# PicKit2-v1_2.net
KiCad netlist of a schematic drawn in EAGLE
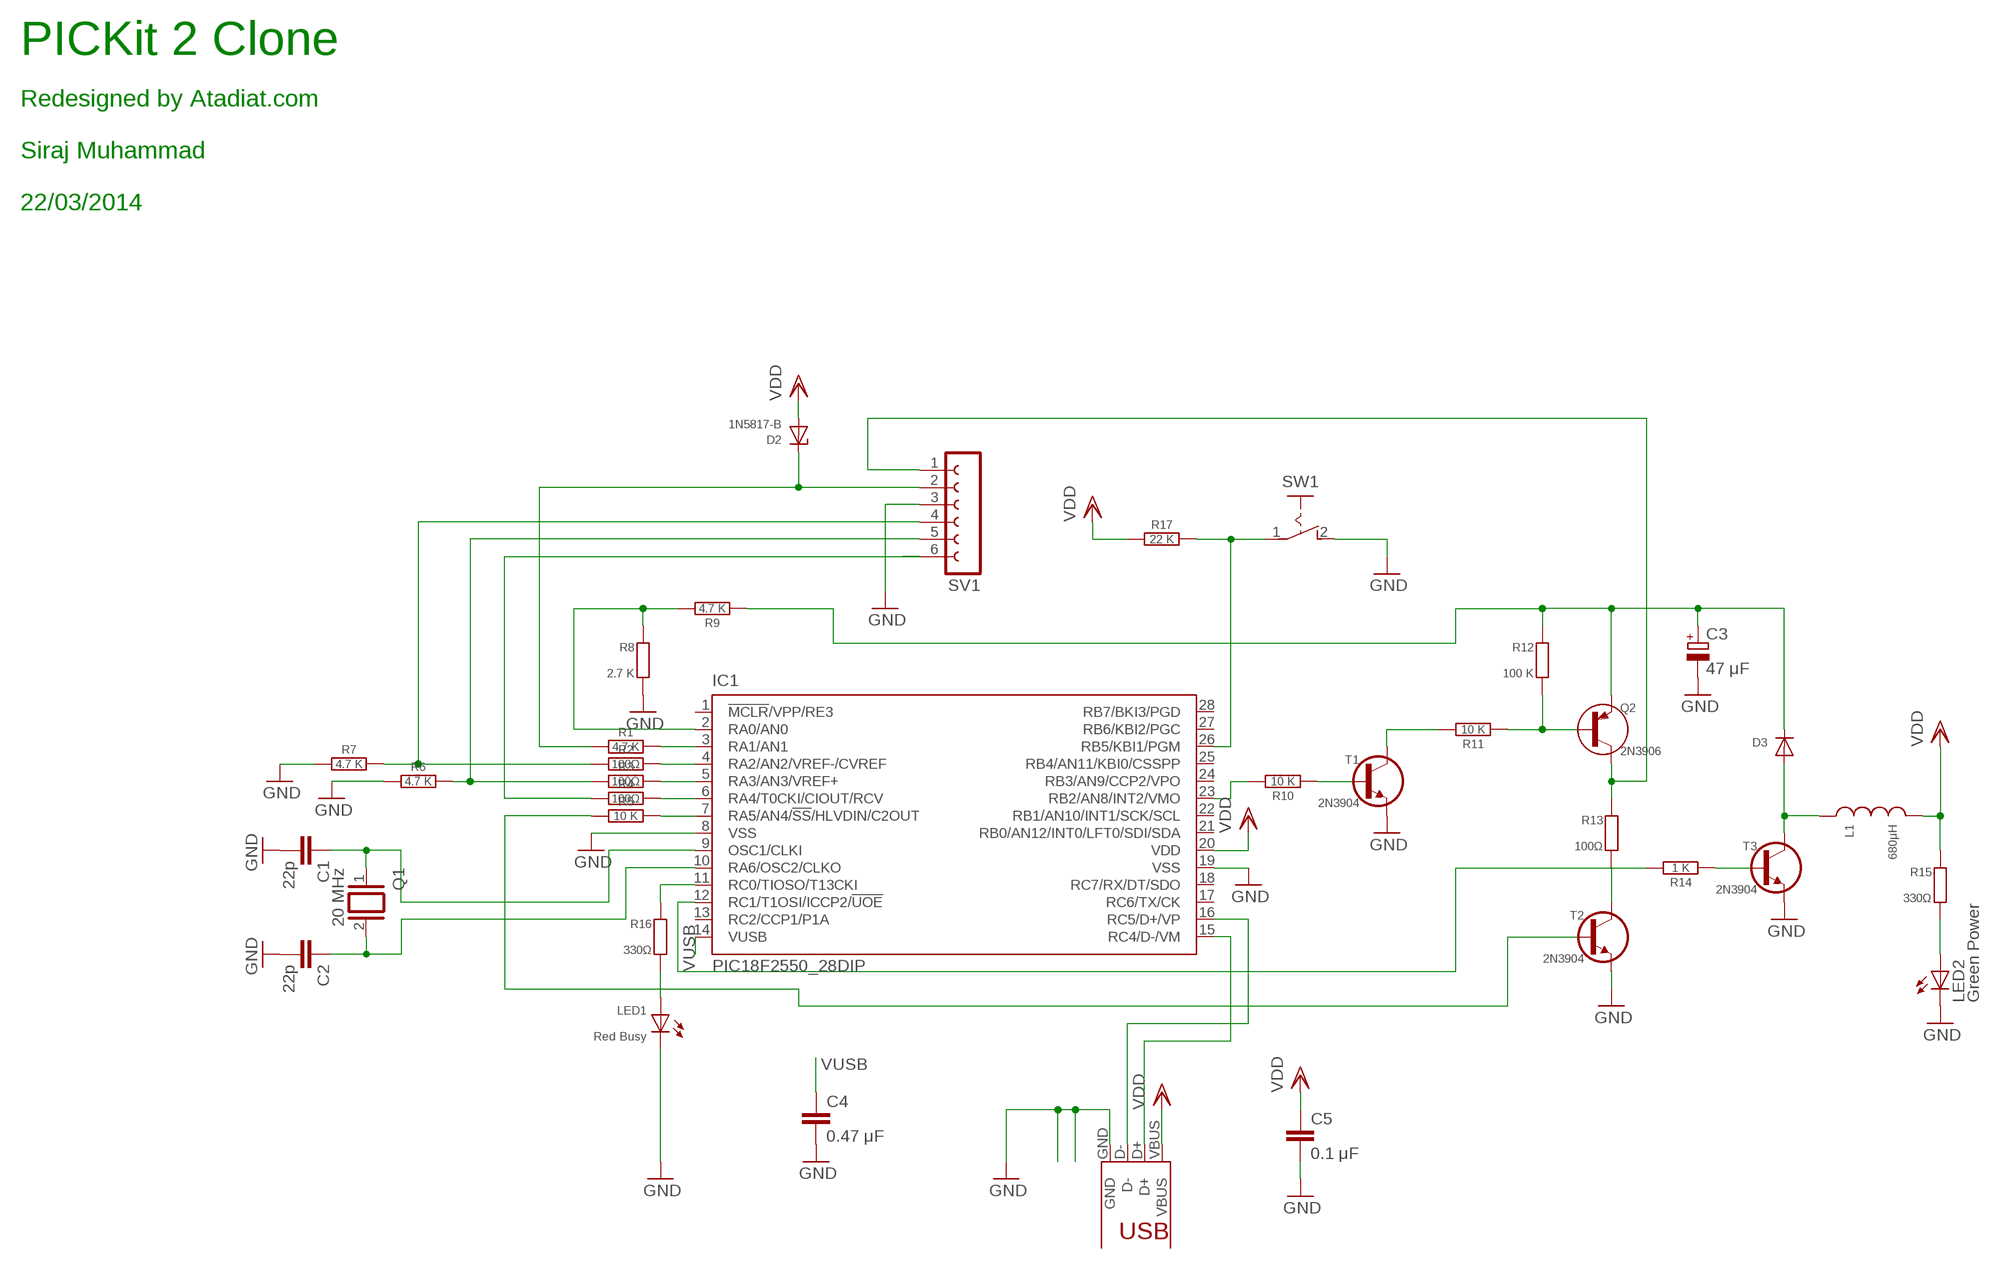
[diagram p0: schematic, sheet 1]

(export (version "E")
  (design (tool "Eeschema 10.0.6"))
  (components
    (comp (ref "C1")
      (value "22p")
      (footprint "eagle-import:C025-020X036")
      (libsource (lib "eagle-import") (part "C025-020X036"))
    )
    (comp (ref "C2")
      (value "22p")
      (footprint "eagle-import:C025-020X036")
      (libsource (lib "eagle-import") (part "C025-020X036"))
    )
    (comp (ref "C3")
      (value "47 μF")
      (footprint "eagle-import:E2,5-6E")
      (libsource (lib "eagle-import") (part "CPOL-EUE2,5-6E"))
    )
    (comp (ref "C4")
      (value "0.47 μF")
      (footprint "eagle-import:C050-030X075")
      (libsource (lib "eagle-import") (part "C050-030X075"))
    )
    (comp (ref "C5")
      (value "0.1 μF")
      (footprint "eagle-import:C050-024X044")
      (libsource (lib "eagle-import") (part "C050-024X044"))
    )
    (comp (ref "D2")
      (value "1N5817-B")
      (footprint "eagle-import:DO34Z10")
      (libsource (lib "eagle-import") (part "Z-DIODE34Z10"))
    )
    (comp (ref "D3")
      (value "DIODE34-10")
      (footprint "eagle-import:DO34-10")
      (libsource (lib "eagle-import") (part "DIODE34-10"))
    )
    (comp (ref "IC1")
      (value "PIC18F2550_28DIP")
      (footprint "eagle-import:DIL28-3")
      (fields (field (name "MF") "MICROCHIP") (field (name "MPN") "PIC18F2550-I/SP"))
      (libsource (lib "eagle-import") (part "PIC18F2_28DIP550"))
    )
    (comp (ref "J1")
      (value "USB-PRINT")
      (footprint "eagle-import:USB-B-PRINT")
      (libsource (lib "eagle-import") (part "USB-PRINT"))
    )
    (comp (ref "L1")
      (value "680μH")
      (footprint "eagle-import:L-8R")
      (libsource (lib "eagle-import") (part "L-09R"))
    )
    (comp (ref "LED1")
      (value "Red Busy")
      (footprint "eagle-import:LED_3MM")
      (libsource (lib "eagle-import") (part "LED-3MM"))
    )
    (comp (ref "LED2")
      (value "Green Power")
      (footprint "eagle-import:LED3MM")
      (libsource (lib "eagle-import") (part "LED3MM"))
    )
    (comp (ref "Q1")
      (value "20 MHz")
      (footprint "eagle-import:QS")
      (libsource (lib "eagle-import") (part "XTAL/S"))
    )
    (comp (ref "Q2")
      (value "2N3906")
      (footprint "eagle-import:TO92")
      (libsource (lib "eagle-import") (part "2N3906"))
    )
    (comp (ref "R1")
      (value "4.7 K")
      (footprint "eagle-import:0204_10")
      (libsource (lib "eagle-import") (part "R-H0204/10"))
    )
    (comp (ref "R2")
      (value "100Ω")
      (footprint "eagle-import:0204_10")
      (libsource (lib "eagle-import") (part "R-H0204/10"))
    )
    (comp (ref "R3")
      (value "100Ω")
      (footprint "eagle-import:0204_10")
      (libsource (lib "eagle-import") (part "R-H0204/10"))
    )
    (comp (ref "R4")
      (value "100Ω")
      (footprint "eagle-import:0204_10")
      (libsource (lib "eagle-import") (part "R-H0204/10"))
    )
    (comp (ref "R5")
      (value "10 K")
      (footprint "eagle-import:0204_10")
      (libsource (lib "eagle-import") (part "R-H0204/10"))
    )
    (comp (ref "R6")
      (value "4.7 K")
      (footprint "eagle-import:0204_10")
      (libsource (lib "eagle-import") (part "R-H0204/10"))
    )
    (comp (ref "R7")
      (value "4.7 K")
      (footprint "eagle-import:0204_10")
      (libsource (lib "eagle-import") (part "R-H0204/10"))
    )
    (comp (ref "R8")
      (value "2.7 K")
      (footprint "eagle-import:0204_10")
      (libsource (lib "eagle-import") (part "R0204/10"))
    )
    (comp (ref "R9")
      (value "4.7 K")
      (footprint "eagle-import:0204_10")
      (libsource (lib "eagle-import") (part "R-H0204/10"))
    )
    (comp (ref "R10")
      (value "10 K")
      (footprint "eagle-import:0204_10")
      (libsource (lib "eagle-import") (part "R-H0204/10"))
    )
    (comp (ref "R11")
      (value "10 K")
      (footprint "eagle-import:0204_10")
      (libsource (lib "eagle-import") (part "R-H0204/10"))
    )
    (comp (ref "R12")
      (value "100 K")
      (footprint "eagle-import:0204_10")
      (libsource (lib "eagle-import") (part "R0204/10"))
    )
    (comp (ref "R13")
      (value "100Ω")
      (footprint "eagle-import:0204_10")
      (libsource (lib "eagle-import") (part "R0204/10"))
    )
    (comp (ref "R14")
      (value "1 K")
      (footprint "eagle-import:0204_10")
      (libsource (lib "eagle-import") (part "R-H0204/10"))
    )
    (comp (ref "R15")
      (value "330Ω")
      (footprint "eagle-import:0204_10")
      (libsource (lib "eagle-import") (part "R0204/10"))
    )
    (comp (ref "R16")
      (value "330Ω")
      (footprint "eagle-import:0204_10")
      (libsource (lib "eagle-import") (part "R0204/10"))
    )
    (comp (ref "R17")
      (value "22 K")
      (footprint "eagle-import:0204_10")
      (libsource (lib "eagle-import") (part "R-H0204/10"))
    )
    (comp (ref "SV1")
      (value "FE06-1")
      (footprint "eagle-import:FE06")
      (libsource (lib "eagle-import") (part "FE06-1"))
    )
    (comp (ref "SW1")
      (value "PB-1P-1T")
      (footprint "eagle-import:PB-1P1T")
      (libsource (lib "eagle-import") (part "PB-1P-1T"))
    )
    (comp (ref "T1")
      (value "2N3904")
      (footprint "eagle-import:TO92")
      (libsource (lib "eagle-import") (part "2N3904"))
    )
    (comp (ref "T2")
      (value "2N3904")
      (footprint "eagle-import:TO92")
      (libsource (lib "eagle-import") (part "2N3904"))
    )
    (comp (ref "T3")
      (value "2N3904")
      (footprint "eagle-import:TO92")
      (libsource (lib "eagle-import") (part "2N3904"))
    )
  )
  (nets
    (net (code "1") (name "/VUSB") (class "Default")
      (node (ref "C4") (pin "1") (pinfunction "1_1") (pintype "passive"))
      (node (ref "IC1") (pin "14") (pinfunction "VUSB_14") (pintype "bidirectional"))
    )
    (net (code "2") (name "GND") (class "Default")
      (node (ref "C1") (pin "2") (pinfunction "2_2") (pintype "passive"))
      (node (ref "C2") (pin "2") (pinfunction "2_2") (pintype "passive"))
      (node (ref "C3") (pin "-") (pinfunction "-_-") (pintype "passive"))
      (node (ref "C4") (pin "2") (pinfunction "2_2") (pintype "passive"))
      (node (ref "C5") (pin "2") (pinfunction "2_2") (pintype "passive"))
      (node (ref "IC1") (pin "19") (pinfunction "VSS_19") (pintype "power_in"))
      (node (ref "IC1") (pin "8") (pinfunction "VSS_8") (pintype "power_in"))
      (node (ref "J1") (pin "GND") (pinfunction "GND_GND") (pintype "bidirectional"))
      (node (ref "LED1") (pin "K") (pinfunction "C_K") (pintype "passive"))
      (node (ref "LED2") (pin "K") (pinfunction "C_K") (pintype "passive"))
      (node (ref "R6") (pin "1") (pinfunction "1_1") (pintype "passive"))
      (node (ref "R7") (pin "1") (pinfunction "1_1") (pintype "passive"))
      (node (ref "R8") (pin "2") (pinfunction "2_2") (pintype "passive"))
      (node (ref "SV1") (pin "3") (pinfunction "3_3") (pintype "passive"))
      (node (ref "SW1") (pin "2") (pinfunction "S_2") (pintype "passive"))
      (node (ref "T1") (pin "1") (pinfunction "E_1") (pintype "passive"))
      (node (ref "T2") (pin "1") (pinfunction "E_1") (pintype "passive"))
      (node (ref "T3") (pin "1") (pinfunction "E_1") (pintype "passive"))
    )
    (net (code "3") (name "Net-(D2-PadC)") (class "Default")
      (node (ref "D2") (pin "C") (pinfunction "C_C") (pintype "passive"))
      (node (ref "R1") (pin "1") (pinfunction "1_1") (pintype "passive"))
      (node (ref "SV1") (pin "2") (pinfunction "2_2") (pintype "passive"))
    )
    (net (code "4") (name "Net-(IC1-OSC1{slash}CLKI)") (class "Default")
      (node (ref "C1") (pin "1") (pinfunction "1_1") (pintype "passive"))
      (node (ref "IC1") (pin "9") (pinfunction "OSC1/CLKI_9") (pintype "input"))
      (node (ref "Q1") (pin "1") (pinfunction "1_1") (pintype "passive"))
    )
    (net (code "5") (name "Net-(IC1-RA0{slash}AN0)") (class "Default")
      (node (ref "IC1") (pin "2") (pinfunction "RA0/AN0_2") (pintype "bidirectional"))
      (node (ref "R8") (pin "1") (pinfunction "1_1") (pintype "passive"))
      (node (ref "R9") (pin "2") (pinfunction "2_2") (pintype "passive"))
    )
    (net (code "6") (name "Net-(IC1-RA1{slash}AN1)") (class "Default")
      (node (ref "IC1") (pin "3") (pinfunction "RA1/AN1_3") (pintype "bidirectional"))
      (node (ref "R1") (pin "2") (pinfunction "2_2") (pintype "passive"))
    )
    (net (code "7") (name "Net-(IC1-RA2{slash}AN2{slash}VREF-{slash}CVREF)") (class "Default")
      (node (ref "IC1") (pin "4") (pinfunction "RA2/AN2/VREF-/CVREF_4") (pintype "bidirectional"))
      (node (ref "R2") (pin "2") (pinfunction "2_2") (pintype "passive"))
    )
    (net (code "8") (name "Net-(IC1-RA3{slash}AN3{slash}VREF+)") (class "Default")
      (node (ref "IC1") (pin "5") (pinfunction "RA3/AN3/VREF+_5") (pintype "bidirectional"))
      (node (ref "R3") (pin "2") (pinfunction "2_2") (pintype "passive"))
    )
    (net (code "9") (name "Net-(IC1-RA4{slash}T0CKI{slash}CIOUT{slash}RCV)") (class "Default")
      (node (ref "IC1") (pin "6") (pinfunction "RA4/T0CKI/CIOUT/RCV_6") (pintype "bidirectional"))
      (node (ref "R4") (pin "2") (pinfunction "2_2") (pintype "passive"))
    )
    (net (code "10") (name "Net-(IC1-RA5{slash}AN4{slash}~{SS}{slash}HLVDIN{slash}C2OUT)") (class "Default")
      (node (ref "IC1") (pin "7") (pinfunction "RA5/AN4/~{SS}/HLVDIN/C2OUT_7") (pintype "bidirectional"))
      (node (ref "R5") (pin "2") (pinfunction "2_2") (pintype "passive"))
    )
    (net (code "11") (name "Net-(IC1-RA6{slash}OSC2{slash}CLKO)") (class "Default")
      (node (ref "C2") (pin "1") (pinfunction "1_1") (pintype "passive"))
      (node (ref "IC1") (pin "10") (pinfunction "RA6/OSC2/CLKO_10") (pintype "output"))
      (node (ref "Q1") (pin "2") (pinfunction "2_2") (pintype "passive"))
    )
    (net (code "12") (name "Net-(IC1-RB2{slash}AN8{slash}INT2{slash}VMO)") (class "Default")
      (node (ref "IC1") (pin "23") (pinfunction "RB2/AN8/INT2/VMO_23") (pintype "bidirectional"))
      (node (ref "R10") (pin "2") (pinfunction "2_2") (pintype "passive"))
    )
    (net (code "13") (name "Net-(IC1-RB5{slash}KBI1{slash}PGM)") (class "Default")
      (node (ref "IC1") (pin "26") (pinfunction "RB5/KBI1/PGM_26") (pintype "bidirectional"))
      (node (ref "R17") (pin "2") (pinfunction "2_2") (pintype "passive"))
      (node (ref "SW1") (pin "1") (pinfunction "P_1") (pintype "passive"))
    )
    (net (code "14") (name "Net-(IC1-RC0{slash}TIOSO{slash}T13CKI)") (class "Default")
      (node (ref "IC1") (pin "11") (pinfunction "RC0/TIOSO/T13CKI_11") (pintype "bidirectional"))
      (node (ref "R16") (pin "1") (pinfunction "1_1") (pintype "passive"))
    )
    (net (code "15") (name "Net-(IC1-RC1{slash}T1OSI{slash}ICCP2{slash}~{UOE})") (class "Default")
      (node (ref "IC1") (pin "12") (pinfunction "RC1/T1OSI/ICCP2/~{UOE}_12") (pintype "bidirectional"))
      (node (ref "R14") (pin "2") (pinfunction "2_2") (pintype "passive"))
    )
    (net (code "16") (name "Net-(IC1-RC4{slash}D-{slash}VM)") (class "Default")
      (node (ref "IC1") (pin "15") (pinfunction "RC4/D-/VM_15") (pintype "bidirectional"))
      (node (ref "J1") (pin "D+") (pinfunction "D+_D+") (pintype "bidirectional"))
    )
    (net (code "17") (name "Net-(IC1-RC5{slash}D+{slash}VP)") (class "Default")
      (node (ref "IC1") (pin "16") (pinfunction "RC5/D+/VP_16") (pintype "bidirectional"))
      (node (ref "J1") (pin "D-") (pinfunction "D-_D-") (pintype "bidirectional"))
    )
    (net (code "18") (name "Net-(L1-1)") (class "Default")
      (node (ref "D3") (pin "A") (pinfunction "A_A") (pintype "passive"))
      (node (ref "L1") (pin "P$1") (pinfunction "1_P$1") (pintype "passive"))
      (node (ref "T3") (pin "3") (pinfunction "C_3") (pintype "passive"))
    )
    (net (code "19") (name "Net-(LED1-PadA)") (class "Default")
      (node (ref "LED1") (pin "A") (pinfunction "A_A") (pintype "passive"))
      (node (ref "R16") (pin "2") (pinfunction "2_2") (pintype "passive"))
    )
    (net (code "20") (name "Net-(LED2-PadA)") (class "Default")
      (node (ref "LED2") (pin "A") (pinfunction "A_A") (pintype "passive"))
      (node (ref "R15") (pin "2") (pinfunction "2_2") (pintype "passive"))
    )
    (net (code "21") (name "Net-(Q2-B)") (class "Default")
      (node (ref "Q2") (pin "2") (pinfunction "B_2") (pintype "passive"))
      (node (ref "R11") (pin "1") (pinfunction "1_1") (pintype "passive"))
      (node (ref "R12") (pin "2") (pinfunction "2_2") (pintype "passive"))
    )
    (net (code "22") (name "Net-(Q2-C)") (class "Default")
      (node (ref "Q2") (pin "3") (pinfunction "C_3") (pintype "passive"))
      (node (ref "R13") (pin "1") (pinfunction "1_1") (pintype "passive"))
      (node (ref "SV1") (pin "1") (pinfunction "1_1") (pintype "passive"))
    )
    (net (code "23") (name "Net-(Q2-E)") (class "Default")
      (node (ref "C3") (pin "+") (pinfunction "+_+") (pintype "passive"))
      (node (ref "D3") (pin "C") (pinfunction "C_C") (pintype "passive"))
      (node (ref "Q2") (pin "1") (pinfunction "E_1") (pintype "passive"))
      (node (ref "R12") (pin "1") (pinfunction "1_1") (pintype "passive"))
      (node (ref "R9") (pin "1") (pinfunction "1_1") (pintype "passive"))
    )
    (net (code "24") (name "Net-(R2-Pad1)") (class "Default")
      (node (ref "R2") (pin "1") (pinfunction "1_1") (pintype "passive"))
      (node (ref "R7") (pin "2") (pinfunction "2_2") (pintype "passive"))
      (node (ref "SV1") (pin "4") (pinfunction "4_4") (pintype "passive"))
    )
    (net (code "25") (name "Net-(R3-Pad1)") (class "Default")
      (node (ref "R3") (pin "1") (pinfunction "1_1") (pintype "passive"))
      (node (ref "R6") (pin "2") (pinfunction "2_2") (pintype "passive"))
      (node (ref "SV1") (pin "5") (pinfunction "5_5") (pintype "passive"))
    )
    (net (code "26") (name "Net-(R4-Pad1)") (class "Default")
      (node (ref "R4") (pin "1") (pinfunction "1_1") (pintype "passive"))
      (node (ref "SV1") (pin "6") (pinfunction "6_6") (pintype "passive"))
    )
    (net (code "27") (name "Net-(T1-B)") (class "Default")
      (node (ref "R10") (pin "1") (pinfunction "1_1") (pintype "passive"))
      (node (ref "T1") (pin "2") (pinfunction "B_2") (pintype "passive"))
    )
    (net (code "28") (name "Net-(T1-C)") (class "Default")
      (node (ref "R11") (pin "2") (pinfunction "2_2") (pintype "passive"))
      (node (ref "T1") (pin "3") (pinfunction "C_3") (pintype "passive"))
    )
    (net (code "29") (name "Net-(T2-B)") (class "Default")
      (node (ref "R5") (pin "1") (pinfunction "1_1") (pintype "passive"))
      (node (ref "T2") (pin "2") (pinfunction "B_2") (pintype "passive"))
    )
    (net (code "30") (name "Net-(T2-C)") (class "Default")
      (node (ref "R13") (pin "2") (pinfunction "2_2") (pintype "passive"))
      (node (ref "T2") (pin "3") (pinfunction "C_3") (pintype "passive"))
    )
    (net (code "31") (name "Net-(T3-B)") (class "Default")
      (node (ref "R14") (pin "1") (pinfunction "1_1") (pintype "passive"))
      (node (ref "T3") (pin "2") (pinfunction "B_2") (pintype "passive"))
    )
    (net (code "32") (name "VDD") (class "Default")
      (node (ref "C5") (pin "1") (pinfunction "1_1") (pintype "passive"))
      (node (ref "D2") (pin "A") (pinfunction "A_A") (pintype "passive"))
      (node (ref "IC1") (pin "20") (pinfunction "VDD_20") (pintype "power_in"))
      (node (ref "J1") (pin "VBUS") (pinfunction "VBUS_VBUS") (pintype "bidirectional"))
      (node (ref "L1") (pin "P$2") (pinfunction "2_P$2") (pintype "passive"))
      (node (ref "R15") (pin "1") (pinfunction "1_1") (pintype "passive"))
      (node (ref "R17") (pin "1") (pinfunction "1_1") (pintype "passive"))
    )
    (net (code "33") (name "unconnected-(IC1-RB0{slash}AN12{slash}INT0{slash}LFT0{slash}SDI{slash}SDA-Pad21)") (class "Default")
      (node (ref "IC1") (pin "21") (pinfunction "RB0/AN12/INT0/LFT0/SDI/SDA_21") (pintype "bidirectional"))
    )
    (net (code "34") (name "unconnected-(IC1-RB1{slash}AN10{slash}INT1{slash}SCK{slash}SCL-Pad22)") (class "Default")
      (node (ref "IC1") (pin "22") (pinfunction "RB1/AN10/INT1/SCK/SCL_22") (pintype "bidirectional"))
    )
    (net (code "35") (name "unconnected-(IC1-RB3{slash}AN9{slash}CCP2{slash}VPO-Pad24)") (class "Default")
      (node (ref "IC1") (pin "24") (pinfunction "RB3/AN9/CCP2/VPO_24") (pintype "bidirectional"))
    )
    (net (code "36") (name "unconnected-(IC1-RB4{slash}AN11{slash}KBI0{slash}CSSPP-Pad25)") (class "Default")
      (node (ref "IC1") (pin "25") (pinfunction "RB4/AN11/KBI0/CSSPP_25") (pintype "bidirectional"))
    )
    (net (code "37") (name "unconnected-(IC1-RB6{slash}KBI2{slash}PGC-Pad27)") (class "Default")
      (node (ref "IC1") (pin "27") (pinfunction "RB6/KBI2/PGC_27") (pintype "bidirectional"))
    )
    (net (code "38") (name "unconnected-(IC1-RB7{slash}BKI3{slash}PGD-Pad28)") (class "Default")
      (node (ref "IC1") (pin "28") (pinfunction "RB7/BKI3/PGD_28") (pintype "bidirectional"))
    )
    (net (code "39") (name "unconnected-(IC1-RC2{slash}CCP1{slash}P1A-Pad13)") (class "Default")
      (node (ref "IC1") (pin "13") (pinfunction "RC2/CCP1/P1A_13") (pintype "bidirectional"))
    )
    (net (code "40") (name "unconnected-(IC1-RC6{slash}TX{slash}CK-Pad17)") (class "Default")
      (node (ref "IC1") (pin "17") (pinfunction "RC6/TX/CK_17") (pintype "bidirectional"))
    )
    (net (code "41") (name "unconnected-(IC1-RC7{slash}RX{slash}DT{slash}SDO-Pad18)") (class "Default")
      (node (ref "IC1") (pin "18") (pinfunction "RC7/RX/DT/SDO_18") (pintype "bidirectional"))
    )
    (net (code "42") (name "unconnected-(IC1-~{MCLR}{slash}VPP{slash}RE3-Pad1)") (class "Default")
      (node (ref "IC1") (pin "1") (pinfunction "~{MCLR}/VPP/RE3_1") (pintype "input"))
    )
  )
)
